# amp.net
KiCad netlist of a schematic drawn in EAGLE
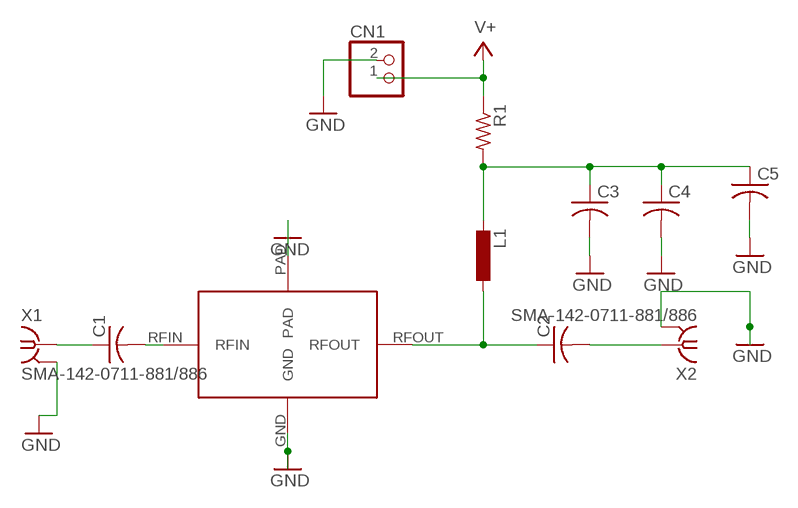
[diagram p0: schematic, sheet 1]

(export (version "E")
  (design (tool "Eeschema 10.0.6"))
  (components
    (comp (ref "C1")
      (value "C-USC0603")
      (footprint "eagle-import:C0603")
      (libsource (lib "eagle-import") (part "C-USC0603"))
    )
    (comp (ref "C2")
      (value "C-USC0603")
      (footprint "eagle-import:C0603")
      (libsource (lib "eagle-import") (part "C-USC0603"))
    )
    (comp (ref "C3")
      (value "C-USC0603")
      (footprint "eagle-import:C0603")
      (libsource (lib "eagle-import") (part "C-USC0603"))
    )
    (comp (ref "C4")
      (value "C-USC0603")
      (footprint "eagle-import:C0603")
      (libsource (lib "eagle-import") (part "C-USC0603"))
    )
    (comp (ref "C5")
      (value "C-USC0603")
      (footprint "eagle-import:C0603")
      (libsource (lib "eagle-import") (part "C-USC0603"))
    )
    (comp (ref "CN1")
      (value "JST_2PIN-THM")
      (footprint "eagle-import:JST-PH-2-THM")
      (libsource (lib "eagle-import") (part "JST_2PIN-THM"))
    )
    (comp (ref "L1")
      (value "L-EUL0603")
      (footprint "eagle-import:L0603")
      (libsource (lib "eagle-import") (part "L-EUL0603"))
    )
    (comp (ref "R1")
      (value "R-US_R0603")
      (footprint "eagle-import:R0603")
      (libsource (lib "eagle-import") (part "R-US_R0603"))
    )
    (comp (ref "U$1")
      (value "MMG3001")
      (footprint "eagle-import:SOT-89")
      (libsource (lib "eagle-import") (part "MMG3001"))
    )
    (comp (ref "X1")
      (value "SMA-142-0711-881/886")
      (footprint "eagle-import:J502-ND-142-0711-881_886")
      (fields (field (name "MF") "JOHNSON COMPONENTS") (field (name "MPN") "142-0711-881"))
      (libsource (lib "eagle-import") (part "SMA-142-0711-881/886"))
    )
    (comp (ref "X2")
      (value "SMA-142-0711-881/886")
      (footprint "eagle-import:J502-ND-142-0711-881_886")
      (fields (field (name "MF") "JOHNSON COMPONENTS") (field (name "MPN") "142-0711-881"))
      (libsource (lib "eagle-import") (part "SMA-142-0711-881/886"))
    )
  )
  (nets
    (net (code "1") (name "GND") (class "Default")
      (node (ref "C3") (pin "2") (pinfunction "2_2") (pintype "passive"))
      (node (ref "C4") (pin "2") (pinfunction "2_2") (pintype "passive"))
      (node (ref "C5") (pin "2") (pinfunction "2_2") (pintype "passive"))
      (node (ref "CN1") (pin "2") (pinfunction "1_2") (pintype "passive"))
      (node (ref "U$1") (pin "GND") (pinfunction "GND_GND") (pintype "bidirectional"))
      (node (ref "U$1") (pin "PAD") (pinfunction "PAD_PAD") (pintype "bidirectional"))
      (node (ref "X1") (pin "G@1") (pinfunction "2_G@1") (pintype "passive"))
      (node (ref "X1") (pin "G@2") (pinfunction "2_G@2") (pintype "passive"))
      (node (ref "X1") (pin "G@3") (pinfunction "2_G@3") (pintype "passive"))
      (node (ref "X1") (pin "G@4") (pinfunction "2_G@4") (pintype "passive"))
      (node (ref "X2") (pin "G@1") (pinfunction "2_G@1") (pintype "passive"))
      (node (ref "X2") (pin "G@2") (pinfunction "2_G@2") (pintype "passive"))
      (node (ref "X2") (pin "G@3") (pinfunction "2_G@3") (pintype "passive"))
      (node (ref "X2") (pin "G@4") (pinfunction "2_G@4") (pintype "passive"))
    )
    (net (code "2") (name "Net-(C1-Pad1)") (class "Default")
      (node (ref "C1") (pin "1") (pinfunction "1_1") (pintype "passive"))
      (node (ref "X1") (pin "1") (pinfunction "1_1") (pintype "passive"))
    )
    (net (code "3") (name "Net-(C1-Pad2)") (class "Default")
      (node (ref "C1") (pin "2") (pinfunction "2_2") (pintype "passive"))
      (node (ref "U$1") (pin "RFIN") (pinfunction "RFIN_RFIN") (pintype "bidirectional"))
    )
    (net (code "4") (name "Net-(C2-Pad1)") (class "Default")
      (node (ref "C2") (pin "1") (pinfunction "1_1") (pintype "passive"))
      (node (ref "L1") (pin "1") (pinfunction "1_1") (pintype "passive"))
      (node (ref "U$1") (pin "RFOUT") (pinfunction "RFOUT_RFOUT") (pintype "bidirectional"))
    )
    (net (code "5") (name "Net-(C2-Pad2)") (class "Default")
      (node (ref "C2") (pin "2") (pinfunction "2_2") (pintype "passive"))
      (node (ref "X2") (pin "1") (pinfunction "1_1") (pintype "passive"))
    )
    (net (code "6") (name "Net-(C3-Pad1)") (class "Default")
      (node (ref "C3") (pin "1") (pinfunction "1_1") (pintype "passive"))
      (node (ref "C4") (pin "1") (pinfunction "1_1") (pintype "passive"))
      (node (ref "C5") (pin "1") (pinfunction "1_1") (pintype "passive"))
      (node (ref "L1") (pin "2") (pinfunction "2_2") (pintype "passive"))
      (node (ref "R1") (pin "2") (pinfunction "2_2") (pintype "passive"))
    )
    (net (code "7") (name "V+") (class "Default")
      (node (ref "CN1") (pin "1") (pinfunction "2_1") (pintype "passive"))
      (node (ref "R1") (pin "1") (pinfunction "1_1") (pintype "passive"))
    )
  )
)
